# Bare_Bones_Arduino.net
KiCad netlist of a schematic drawn in EAGLE
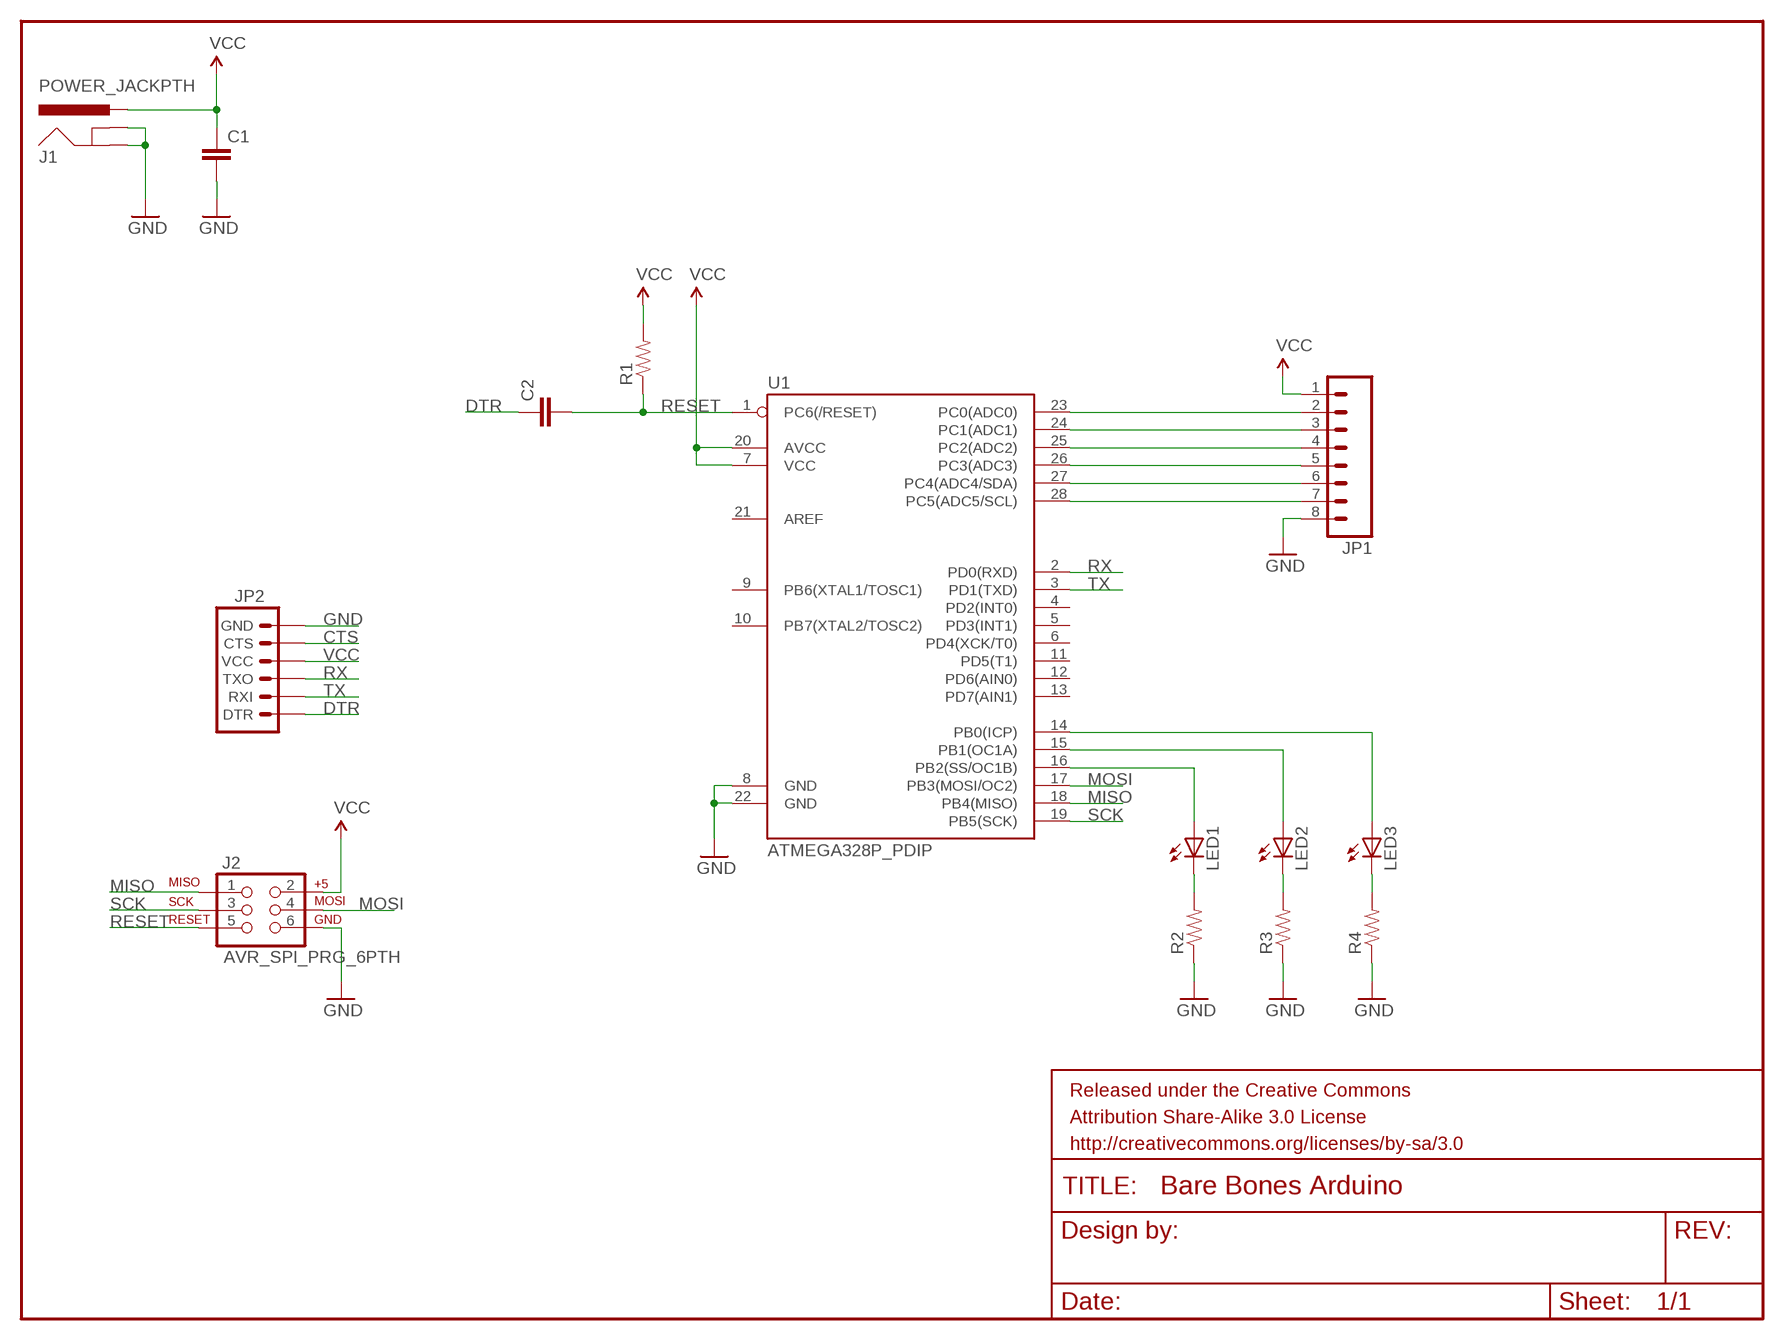
[diagram p0: schematic, sheet 1]

(export (version "E")
  (design (tool "Eeschema 10.0.6"))
  (components
    (comp (ref "C1")
      (value "CAPPTH")
      (footprint "eagle-import:CAP-PTH-SMALL")
      (libsource (lib "eagle-import") (part "CAPPTH"))
    )
    (comp (ref "C2")
      (value "CAPPTH")
      (footprint "eagle-import:CAP-PTH-SMALL")
      (libsource (lib "eagle-import") (part "CAPPTH"))
    )
    (comp (ref "FRAME1")
      (value "FRAME-LETTER")
      (footprint "eagle-import:CREATIVE_COMMONS")
      (libsource (lib "eagle-import") (part "FRAME-LETTER"))
    )
    (comp (ref "J1")
      (value "POWER_JACKPTH")
      (footprint "eagle-import:POWER_JACK_PTH")
      (libsource (lib "eagle-import") (part "POWER_JACKPTH"))
    )
    (comp (ref "J2")
      (value "AVR_SPI_PRG_6PTH")
      (footprint "eagle-import:2X3")
      (libsource (lib "eagle-import") (part "AVR_SPI_PRG_6PTH"))
    )
    (comp (ref "JP1")
      (value "M081X08")
      (footprint "eagle-import:1X08")
      (libsource (lib "eagle-import") (part "M081X08"))
    )
    (comp (ref "JP2")
      (value "ARDUINO_SERIAL_PROGRAMPTH")
      (footprint "eagle-import:1X06")
      (libsource (lib "eagle-import") (part "ARDUINO_SERIAL_PROGRAMPTH"))
    )
    (comp (ref "LED1")
      (value "LED5MM")
      (footprint "eagle-import:LED5MM")
      (libsource (lib "eagle-import") (part "LED5MM"))
    )
    (comp (ref "LED2")
      (value "LED5MM")
      (footprint "eagle-import:LED5MM")
      (libsource (lib "eagle-import") (part "LED5MM"))
    )
    (comp (ref "LED3")
      (value "LED5MM")
      (footprint "eagle-import:LED5MM")
      (libsource (lib "eagle-import") (part "LED5MM"))
    )
    (comp (ref "R1")
      (value "RESISTORPTH-1/4W")
      (footprint "eagle-import:AXIAL-0.4")
      (libsource (lib "eagle-import") (part "RESISTORPTH-1/4W"))
    )
    (comp (ref "R2")
      (value "RESISTORPTH-1/4W")
      (footprint "eagle-import:AXIAL-0.4")
      (libsource (lib "eagle-import") (part "RESISTORPTH-1/4W"))
    )
    (comp (ref "R3")
      (value "RESISTORPTH-1/4W")
      (footprint "eagle-import:AXIAL-0.4")
      (libsource (lib "eagle-import") (part "RESISTORPTH-1/4W"))
    )
    (comp (ref "R4")
      (value "RESISTORPTH-1/4W")
      (footprint "eagle-import:AXIAL-0.4")
      (libsource (lib "eagle-import") (part "RESISTORPTH-1/4W"))
    )
    (comp (ref "U1")
      (value "ATMEGA328P_PDIP")
      (footprint "eagle-import:DIL28-3")
      (libsource (lib "eagle-import") (part "ATMEGA328P_PDIP"))
    )
  )
  (nets
    (net (code "1") (name "/CTS") (class "Default")
      (node (ref "JP2") (pin "5") (pinfunction "CTS_5") (pintype "passive"))
    )
    (net (code "2") (name "/DTR") (class "Default")
      (node (ref "C2") (pin "1") (pinfunction "1_1") (pintype "passive"))
      (node (ref "JP2") (pin "1") (pinfunction "DTR_1") (pintype "passive"))
    )
    (net (code "3") (name "/MISO") (class "Default")
      (node (ref "J2") (pin "1") (pinfunction "1_1") (pintype "passive"))
      (node (ref "U1") (pin "18") (pinfunction "PB4(MISO)_18") (pintype "bidirectional"))
    )
    (net (code "4") (name "/MOSI") (class "Default")
      (node (ref "J2") (pin "4") (pinfunction "4_4") (pintype "passive"))
      (node (ref "U1") (pin "17") (pinfunction "PB3(MOSI/OC2)_17") (pintype "bidirectional"))
    )
    (net (code "5") (name "/RESET") (class "Default")
      (node (ref "C2") (pin "2") (pinfunction "2_2") (pintype "passive"))
      (node (ref "J2") (pin "5") (pinfunction "5_5") (pintype "passive"))
      (node (ref "R1") (pin "P$1") (pinfunction "1_P$1") (pintype "passive"))
      (node (ref "U1") (pin "1") (pinfunction "PC6(/RESET)_1") (pintype "bidirectional"))
    )
    (net (code "6") (name "/RX") (class "Default")
      (node (ref "JP2") (pin "3") (pinfunction "TXO_3") (pintype "passive"))
      (node (ref "U1") (pin "2") (pinfunction "PD0(RXD)_2") (pintype "bidirectional"))
    )
    (net (code "7") (name "/SCK") (class "Default")
      (node (ref "J2") (pin "3") (pinfunction "3_3") (pintype "passive"))
      (node (ref "U1") (pin "19") (pinfunction "PB5(SCK)_19") (pintype "bidirectional"))
    )
    (net (code "8") (name "/TX") (class "Default")
      (node (ref "JP2") (pin "2") (pinfunction "RXI_2") (pintype "passive"))
      (node (ref "U1") (pin "3") (pinfunction "PD1(TXD)_3") (pintype "bidirectional"))
    )
    (net (code "9") (name "GND") (class "Default")
      (node (ref "C1") (pin "2") (pinfunction "2_2") (pintype "passive"))
      (node (ref "J1") (pin "GND") (pinfunction "GND_GND") (pintype "bidirectional"))
      (node (ref "J1") (pin "GNDBREAK") (pinfunction "GNDBREAK_GNDBREAK") (pintype "bidirectional"))
      (node (ref "J2") (pin "6") (pinfunction "6_6") (pintype "passive"))
      (node (ref "JP1") (pin "8") (pinfunction "8_8") (pintype "passive"))
      (node (ref "JP2") (pin "6") (pinfunction "GND_6") (pintype "passive"))
      (node (ref "R2") (pin "P$1") (pinfunction "1_P$1") (pintype "passive"))
      (node (ref "R3") (pin "P$1") (pinfunction "1_P$1") (pintype "passive"))
      (node (ref "R4") (pin "P$1") (pinfunction "1_P$1") (pintype "passive"))
      (node (ref "U1") (pin "22") (pinfunction "GND_22") (pintype "bidirectional"))
      (node (ref "U1") (pin "8") (pinfunction "GND_8") (pintype "bidirectional"))
    )
    (net (code "10") (name "Net-(LED1-C)") (class "Default")
      (node (ref "LED1") (pin "K") (pinfunction "C_K") (pintype "passive"))
      (node (ref "R2") (pin "P$2") (pinfunction "2_P$2") (pintype "passive"))
    )
    (net (code "11") (name "Net-(LED2-C)") (class "Default")
      (node (ref "LED2") (pin "K") (pinfunction "C_K") (pintype "passive"))
      (node (ref "R3") (pin "P$2") (pinfunction "2_P$2") (pintype "passive"))
    )
    (net (code "12") (name "Net-(LED3-C)") (class "Default")
      (node (ref "LED3") (pin "K") (pinfunction "C_K") (pintype "passive"))
      (node (ref "R4") (pin "P$2") (pinfunction "2_P$2") (pintype "passive"))
    )
    (net (code "13") (name "Net-(U1-PB0(ICP))") (class "Default")
      (node (ref "LED3") (pin "A") (pinfunction "A_A") (pintype "passive"))
      (node (ref "U1") (pin "14") (pinfunction "PB0(ICP)_14") (pintype "bidirectional"))
    )
    (net (code "14") (name "Net-(U1-PB1(OC1A))") (class "Default")
      (node (ref "LED2") (pin "A") (pinfunction "A_A") (pintype "passive"))
      (node (ref "U1") (pin "15") (pinfunction "PB1(OC1A)_15") (pintype "bidirectional"))
    )
    (net (code "15") (name "Net-(U1-PB2(SS{slash}OC1B))") (class "Default")
      (node (ref "LED1") (pin "A") (pinfunction "A_A") (pintype "passive"))
      (node (ref "U1") (pin "16") (pinfunction "PB2(SS/OC1B)_16") (pintype "bidirectional"))
    )
    (net (code "16") (name "Net-(U1-PC0(ADC0))") (class "Default")
      (node (ref "JP1") (pin "2") (pinfunction "2_2") (pintype "passive"))
      (node (ref "U1") (pin "23") (pinfunction "PC0(ADC0)_23") (pintype "bidirectional"))
    )
    (net (code "17") (name "Net-(U1-PC1(ADC1))") (class "Default")
      (node (ref "JP1") (pin "3") (pinfunction "3_3") (pintype "passive"))
      (node (ref "U1") (pin "24") (pinfunction "PC1(ADC1)_24") (pintype "bidirectional"))
    )
    (net (code "18") (name "Net-(U1-PC2(ADC2))") (class "Default")
      (node (ref "JP1") (pin "4") (pinfunction "4_4") (pintype "passive"))
      (node (ref "U1") (pin "25") (pinfunction "PC2(ADC2)_25") (pintype "bidirectional"))
    )
    (net (code "19") (name "Net-(U1-PC3(ADC3))") (class "Default")
      (node (ref "JP1") (pin "5") (pinfunction "5_5") (pintype "passive"))
      (node (ref "U1") (pin "26") (pinfunction "PC3(ADC3)_26") (pintype "bidirectional"))
    )
    (net (code "20") (name "Net-(U1-PC4(ADC4{slash}SDA))") (class "Default")
      (node (ref "JP1") (pin "6") (pinfunction "6_6") (pintype "passive"))
      (node (ref "U1") (pin "27") (pinfunction "PC4(ADC4/SDA)_27") (pintype "bidirectional"))
    )
    (net (code "21") (name "Net-(U1-PC5(ADC5{slash}SCL))") (class "Default")
      (node (ref "JP1") (pin "7") (pinfunction "7_7") (pintype "passive"))
      (node (ref "U1") (pin "28") (pinfunction "PC5(ADC5/SCL)_28") (pintype "bidirectional"))
    )
    (net (code "22") (name "VCC") (class "Default")
      (node (ref "C1") (pin "1") (pinfunction "1_1") (pintype "passive"))
      (node (ref "J1") (pin "PWR") (pinfunction "PWR_PWR") (pintype "bidirectional"))
      (node (ref "J2") (pin "2") (pinfunction "2_2") (pintype "passive"))
      (node (ref "JP1") (pin "1") (pinfunction "1_1") (pintype "passive"))
      (node (ref "JP2") (pin "4") (pinfunction "VCC_4") (pintype "passive"))
      (node (ref "R1") (pin "P$2") (pinfunction "2_P$2") (pintype "passive"))
      (node (ref "U1") (pin "20") (pinfunction "AVCC_20") (pintype "bidirectional"))
      (node (ref "U1") (pin "7") (pinfunction "VCC_7") (pintype "bidirectional"))
    )
    (net (code "23") (name "unconnected-(U1-AREF-Pad21)") (class "Default")
      (node (ref "U1") (pin "21") (pinfunction "AREF_21") (pintype "bidirectional"))
    )
    (net (code "24") (name "unconnected-(U1-PB6(XTAL1{slash}TOSC1)-Pad9)") (class "Default")
      (node (ref "U1") (pin "9") (pinfunction "PB6(XTAL1/TOSC1)_9") (pintype "bidirectional"))
    )
    (net (code "25") (name "unconnected-(U1-PB7(XTAL2{slash}TOSC2)-Pad10)") (class "Default")
      (node (ref "U1") (pin "10") (pinfunction "PB7(XTAL2/TOSC2)_10") (pintype "bidirectional"))
    )
    (net (code "26") (name "unconnected-(U1-PD2(INT0)-Pad4)") (class "Default")
      (node (ref "U1") (pin "4") (pinfunction "PD2(INT0)_4") (pintype "bidirectional"))
    )
    (net (code "27") (name "unconnected-(U1-PD3(INT1)-Pad5)") (class "Default")
      (node (ref "U1") (pin "5") (pinfunction "PD3(INT1)_5") (pintype "bidirectional"))
    )
    (net (code "28") (name "unconnected-(U1-PD4(XCK{slash}T0)-Pad6)") (class "Default")
      (node (ref "U1") (pin "6") (pinfunction "PD4(XCK/T0)_6") (pintype "bidirectional"))
    )
    (net (code "29") (name "unconnected-(U1-PD5(T1)-Pad11)") (class "Default")
      (node (ref "U1") (pin "11") (pinfunction "PD5(T1)_11") (pintype "bidirectional"))
    )
    (net (code "30") (name "unconnected-(U1-PD6(AIN0)-Pad12)") (class "Default")
      (node (ref "U1") (pin "12") (pinfunction "PD6(AIN0)_12") (pintype "bidirectional"))
    )
    (net (code "31") (name "unconnected-(U1-PD7(AIN1)-Pad13)") (class "Default")
      (node (ref "U1") (pin "13") (pinfunction "PD7(AIN1)_13") (pintype "bidirectional"))
    )
  )
)
